# Garage_Interface.net
KiCad netlist of a schematic drawn in Altium Designer
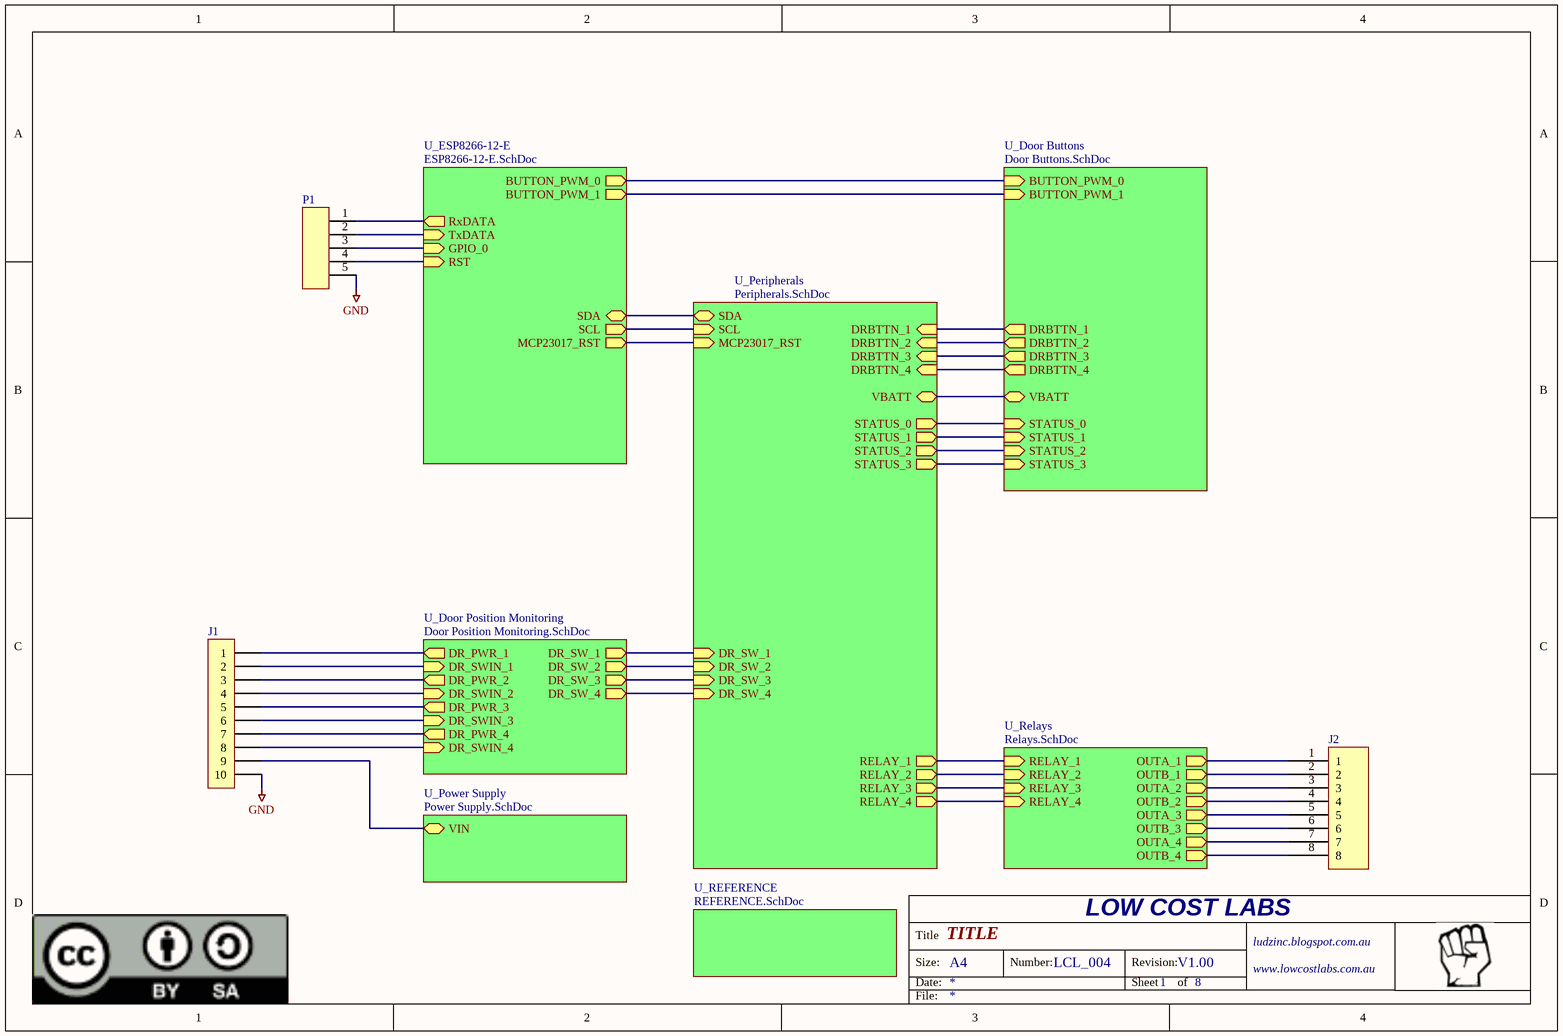
[diagram p0: Garage Interface.SchDoc]

(export (version "E")
  (design (tool "Eeschema 10.0.6"))
  (components
    (comp (ref "J1")
      (value "Phoenix Contact MSTBA 2,5/10-G-5,08-LR")
      (footprint "PCB-724730-1")
      (description "Header, Right Angle, 5.08mm, 10way")
      (fields (field (name "MANUFACTURER PART NUMBER") "MSTBA 2,5/10-G-5,08-LR"))
      (libsource (lib "FavoritesLibrary") (part "SYM-e10a2800e6103ecd-1"))
    )
    (comp (ref "J2")
      (value "Phoenix Contact MSTBA 2,5/ 8-G-5,08-LR")
      (footprint "PCB-724730-1")
      (description "Header, Right Angle, 5.08mm, 8way")
      (fields (field (name "MANUFACTURER PART NUMBER") "MSTBA 2,5/ 8-G-5,08-LR"))
      (libsource (lib "FavoritesLibrary") (part "SYM-724730-1"))
    )
    (comp (ref "P1")
      (value "TE Connectivity 825433-5")
      (footprint "PCB-xti7u9j93a3qzo3mq4li-1")
      (description "Conn Unshrouded Header HDR 5 POS 2.54mm Solder ST Thru-Hole")
      (libsource (lib "FavoritesLibrary") (part "SYM-a17c6af386817ebb-2"))
    )
  )
  (nets
    (net (code "7") (name "/DR_PWR_1") (class "Default")
      (node (ref "J1") (pin "1") (pinfunction "1_1") (pintype "passive"))
    )
    (net (code "8") (name "/DR_PWR_2") (class "Default")
      (node (ref "J1") (pin "3") (pinfunction "3_3") (pintype "passive"))
    )
    (net (code "9") (name "/DR_PWR_3") (class "Default")
      (node (ref "J1") (pin "5") (pinfunction "5_5") (pintype "passive"))
    )
    (net (code "10") (name "/DR_PWR_4") (class "Default")
      (node (ref "J1") (pin "7") (pinfunction "7_7") (pintype "passive"))
    )
    (net (code "11") (name "/DR_SWIN_1") (class "Default")
      (node (ref "J1") (pin "2") (pinfunction "2_2") (pintype "passive"))
    )
    (net (code "12") (name "/DR_SWIN_2") (class "Default")
      (node (ref "J1") (pin "4") (pinfunction "4_4") (pintype "passive"))
    )
    (net (code "13") (name "/DR_SWIN_3") (class "Default")
      (node (ref "J1") (pin "6") (pinfunction "6_6") (pintype "passive"))
    )
    (net (code "14") (name "/DR_SWIN_4") (class "Default")
      (node (ref "J1") (pin "8") (pinfunction "8_8") (pintype "passive"))
    )
    (net (code "19") (name "/GPIO_0") (class "Default")
      (node (ref "P1") (pin "3") (pinfunction "3_3") (pintype "passive"))
    )
    (net (code "21") (name "/OUTA_1") (class "Default")
      (node (ref "J2") (pin "1") (pinfunction "1_1") (pintype "passive"))
    )
    (net (code "22") (name "/OUTA_2") (class "Default")
      (node (ref "J2") (pin "3") (pinfunction "3_3") (pintype "passive"))
    )
    (net (code "23") (name "/OUTA_3") (class "Default")
      (node (ref "J2") (pin "5") (pinfunction "5_5") (pintype "passive"))
    )
    (net (code "24") (name "/OUTA_4") (class "Default")
      (node (ref "J2") (pin "7") (pinfunction "7_7") (pintype "passive"))
    )
    (net (code "25") (name "/OUTB_1") (class "Default")
      (node (ref "J2") (pin "2") (pinfunction "2_2") (pintype "passive"))
    )
    (net (code "26") (name "/OUTB_2") (class "Default")
      (node (ref "J2") (pin "4") (pinfunction "4_4") (pintype "passive"))
    )
    (net (code "27") (name "/OUTB_3") (class "Default")
      (node (ref "J2") (pin "6") (pinfunction "6_6") (pintype "passive"))
    )
    (net (code "28") (name "/OUTB_4") (class "Default")
      (node (ref "J2") (pin "8") (pinfunction "8_8") (pintype "passive"))
    )
    (net (code "33") (name "/RST") (class "Default")
      (node (ref "P1") (pin "4") (pinfunction "4_4") (pintype "passive"))
    )
    (net (code "34") (name "/RxDATA") (class "Default")
      (node (ref "P1") (pin "1") (pinfunction "1_1") (pintype "passive"))
    )
    (net (code "41") (name "/TxDATA") (class "Default")
      (node (ref "P1") (pin "2") (pinfunction "2_2") (pintype "passive"))
    )
    (net (code "43") (name "/VIN") (class "Default")
      (node (ref "J1") (pin "9") (pinfunction "9_9") (pintype "passive"))
    )
    (net (code "44") (name "GND") (class "Default")
      (node (ref "J1") (pin "10") (pinfunction "10_10") (pintype "passive"))
      (node (ref "P1") (pin "5") (pinfunction "5_5") (pintype "passive"))
    )
  )
)
